# CC2500_Module.net
KiCad netlist of a schematic drawn in EAGLE
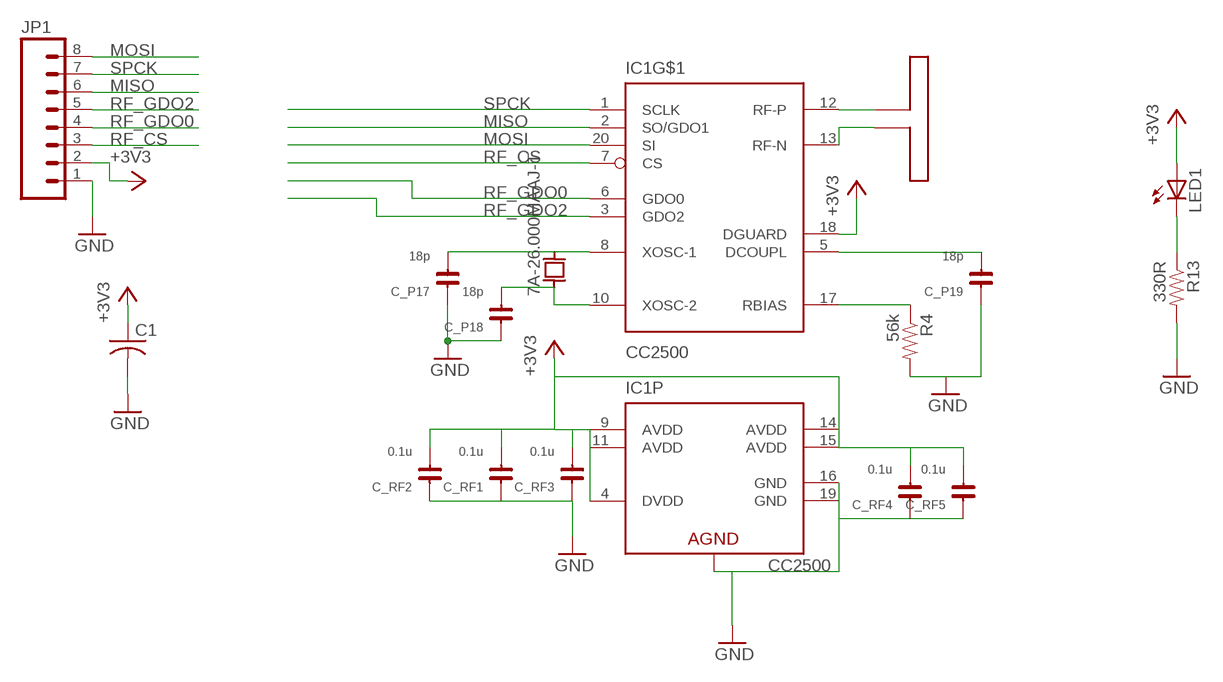
[diagram p0: schematic, sheet 1]

(export (version "E")
  (design (tool "Eeschema 10.0.6"))
  (components
    (comp (ref "C1")
      (value "C-USC1206")
      (footprint "eagle-import:C1206")
      (libsource (lib "eagle-import") (part "C-USC1206"))
    )
    (comp (ref "C_P17")
      (value "18p")
      (footprint "eagle-import:0603-CAP")
      (libsource (lib "eagle-import") (part "CAPACITOR0603-CAP"))
    )
    (comp (ref "C_P18")
      (value "18p")
      (footprint "eagle-import:0603-CAP")
      (libsource (lib "eagle-import") (part "CAPACITOR0603-CAP"))
    )
    (comp (ref "C_P19")
      (value "18p")
      (footprint "eagle-import:0603-CAP")
      (libsource (lib "eagle-import") (part "CAPACITOR0603-CAP"))
    )
    (comp (ref "C_RF1")
      (value "0.1u")
      (footprint "eagle-import:0603-CAP")
      (libsource (lib "eagle-import") (part "CAPACITOR0603-CAP"))
    )
    (comp (ref "C_RF2")
      (value "0.1u")
      (footprint "eagle-import:0603-CAP")
      (libsource (lib "eagle-import") (part "CAPACITOR0603-CAP"))
    )
    (comp (ref "C_RF3")
      (value "0.1u")
      (footprint "eagle-import:0603-CAP")
      (libsource (lib "eagle-import") (part "CAPACITOR0603-CAP"))
    )
    (comp (ref "C_RF4")
      (value "0.1u")
      (footprint "eagle-import:0603-CAP")
      (libsource (lib "eagle-import") (part "CAPACITOR0603-CAP"))
    )
    (comp (ref "C_RF5")
      (value "0.1u")
      (footprint "eagle-import:0603-CAP")
      (libsource (lib "eagle-import") (part "CAPACITOR0603-CAP"))
    )
    (comp (ref "IC1")
      (value "CC2500")
      (footprint "eagle-import:QLP-20")
      (libsource (lib "eagle-import") (part "CC2500"))
    )
    (comp (ref "JP1")
      (value "M081X08")
      (footprint "eagle-import:1X08")
      (libsource (lib "eagle-import") (part "M081X08"))
    )
    (comp (ref "LED1")
      (value "LED1206")
      (footprint "eagle-import:LED-1206")
      (libsource (lib "eagle-import") (part "LED1206"))
    )
    (comp (ref "R4")
      (value "56k")
      (footprint "eagle-import:0402-RES")
      (libsource (lib "eagle-import") (part "RESISTOR0402-RES"))
    )
    (comp (ref "R13")
      (value "330R")
      (footprint "eagle-import:0402-RES")
      (libsource (lib "eagle-import") (part "RESISTOR0402-RES"))
    )
    (comp (ref "U$22")
      (value "ANTENNA_DIPOLE")
      (footprint "eagle-import:CC2500_FOLDED_DIPOLE_ANTENNA")
      (libsource (lib "eagle-import") (part "ANTENNA_DIPOLE"))
    )
    (comp (ref "U$23")
      (value "7A-26.000MAAJ-T")
      (footprint "eagle-import:5X3.2MM_SMD_XTAL")
      (libsource (lib "eagle-import") (part "XTAL_2_PIN5MMX3.2MM"))
    )
  )
  (nets
    (net (code "1") (name "+3V3") (class "Default")
      (node (ref "C1") (pin "1") (pinfunction "1_1") (pintype "passive"))
      (node (ref "C_RF1") (pin "2") (pinfunction "2_2") (pintype "bidirectional"))
      (node (ref "C_RF2") (pin "2") (pinfunction "2_2") (pintype "bidirectional"))
      (node (ref "C_RF3") (pin "2") (pinfunction "2_2") (pintype "bidirectional"))
      (node (ref "C_RF4") (pin "2") (pinfunction "2_2") (pintype "bidirectional"))
      (node (ref "C_RF5") (pin "2") (pinfunction "2_2") (pintype "bidirectional"))
      (node (ref "IC1") (pin "11") (pinfunction "AVDD_11") (pintype "power_in"))
      (node (ref "IC1") (pin "14") (pinfunction "AVDD_14") (pintype "power_in"))
      (node (ref "IC1") (pin "15") (pinfunction "AVDD_15") (pintype "power_in"))
      (node (ref "IC1") (pin "18") (pinfunction "DGUARD_18") (pintype "power_in"))
      (node (ref "IC1") (pin "4") (pinfunction "DVDD_4") (pintype "power_in"))
      (node (ref "IC1") (pin "9") (pinfunction "AVDD_9") (pintype "power_in"))
      (node (ref "JP1") (pin "2") (pinfunction "2_2") (pintype "passive"))
      (node (ref "LED1") (pin "A") (pinfunction "A_A") (pintype "passive"))
    )
    (net (code "2") (name "/MISO") (class "Default")
      (node (ref "IC1") (pin "2") (pinfunction "SO/GDO1_2") (pintype "output"))
      (node (ref "JP1") (pin "6") (pinfunction "6_6") (pintype "passive"))
    )
    (net (code "3") (name "/MOSI") (class "Default")
      (node (ref "IC1") (pin "20") (pinfunction "SI_20") (pintype "input"))
      (node (ref "JP1") (pin "8") (pinfunction "8_8") (pintype "passive"))
    )
    (net (code "4") (name "/RF_CS") (class "Default")
      (node (ref "IC1") (pin "7") (pinfunction "CS_7") (pintype "input"))
      (node (ref "JP1") (pin "3") (pinfunction "3_3") (pintype "passive"))
    )
    (net (code "5") (name "/RF_GDO0") (class "Default")
      (node (ref "IC1") (pin "6") (pinfunction "GDO0_6") (pintype "output"))
      (node (ref "JP1") (pin "4") (pinfunction "4_4") (pintype "passive"))
    )
    (net (code "6") (name "/RF_GDO2") (class "Default")
      (node (ref "IC1") (pin "3") (pinfunction "GDO2_3") (pintype "output"))
      (node (ref "JP1") (pin "5") (pinfunction "5_5") (pintype "passive"))
    )
    (net (code "7") (name "/SPCK") (class "Default")
      (node (ref "IC1") (pin "1") (pinfunction "SCLK_1") (pintype "input"))
      (node (ref "JP1") (pin "7") (pinfunction "7_7") (pintype "passive"))
    )
    (net (code "8") (name "GND") (class "Default")
      (node (ref "C1") (pin "2") (pinfunction "2_2") (pintype "passive"))
      (node (ref "C_P17") (pin "1") (pinfunction "1_1") (pintype "bidirectional"))
      (node (ref "C_P18") (pin "1") (pinfunction "1_1") (pintype "bidirectional"))
      (node (ref "C_P19") (pin "1") (pinfunction "1_1") (pintype "bidirectional"))
      (node (ref "C_RF1") (pin "1") (pinfunction "1_1") (pintype "bidirectional"))
      (node (ref "C_RF2") (pin "1") (pinfunction "1_1") (pintype "bidirectional"))
      (node (ref "C_RF3") (pin "1") (pinfunction "1_1") (pintype "bidirectional"))
      (node (ref "C_RF4") (pin "1") (pinfunction "1_1") (pintype "bidirectional"))
      (node (ref "C_RF5") (pin "1") (pinfunction "1_1") (pintype "bidirectional"))
      (node (ref "IC1") (pin "16") (pinfunction "GND_16") (pintype "power_in"))
      (node (ref "IC1") (pin "19") (pinfunction "GND_19") (pintype "power_in"))
      (node (ref "IC1") (pin "PAD") (pinfunction "AGND_PAD") (pintype "power_in"))
      (node (ref "IC1") (pin "THERMAL1") (pinfunction "AGND_THERMAL1") (pintype "power_in"))
      (node (ref "IC1") (pin "THERMAL2") (pinfunction "AGND_THERMAL2") (pintype "power_in"))
      (node (ref "IC1") (pin "THERMAL3") (pinfunction "AGND_THERMAL3") (pintype "power_in"))
      (node (ref "IC1") (pin "THERMAL4") (pinfunction "AGND_THERMAL4") (pintype "power_in"))
      (node (ref "IC1") (pin "THERMAL5") (pinfunction "AGND_THERMAL5") (pintype "power_in"))
      (node (ref "JP1") (pin "1") (pinfunction "1_1") (pintype "passive"))
      (node (ref "R13") (pin "2") (pinfunction "2_2") (pintype "passive"))
      (node (ref "R4") (pin "2") (pinfunction "2_2") (pintype "passive"))
    )
    (net (code "9") (name "Net-(IC1A-DCOUPL)") (class "Default")
      (node (ref "C_P19") (pin "2") (pinfunction "2_2") (pintype "bidirectional"))
      (node (ref "IC1") (pin "5") (pinfunction "DCOUPL_5") (pintype "power_in"))
    )
    (net (code "10") (name "Net-(IC1A-RBIAS)") (class "Default")
      (node (ref "IC1") (pin "17") (pinfunction "RBIAS_17") (pintype "bidirectional"))
      (node (ref "R4") (pin "1") (pinfunction "1_1") (pintype "passive"))
    )
    (net (code "11") (name "Net-(IC1A-RF-N)") (class "Default")
      (node (ref "IC1") (pin "13") (pinfunction "RF-N_13") (pintype "bidirectional"))
      (node (ref "U$22") (pin "P$2") (pinfunction "P$2_P$2") (pintype "bidirectional"))
    )
    (net (code "12") (name "Net-(IC1A-RF-P)") (class "Default")
      (node (ref "IC1") (pin "12") (pinfunction "RF-P_12") (pintype "bidirectional"))
      (node (ref "U$22") (pin "P$1") (pinfunction "P$1_P$1") (pintype "bidirectional"))
    )
    (net (code "13") (name "Net-(IC1A-XOSC-1)") (class "Default")
      (node (ref "C_P17") (pin "2") (pinfunction "2_2") (pintype "bidirectional"))
      (node (ref "IC1") (pin "8") (pinfunction "XOSC-1_8") (pintype "input"))
      (node (ref "U$23") (pin "X2") (pinfunction "X2_X2") (pintype "bidirectional"))
    )
    (net (code "14") (name "Net-(IC1A-XOSC-2)") (class "Default")
      (node (ref "C_P18") (pin "2") (pinfunction "2_2") (pintype "bidirectional"))
      (node (ref "IC1") (pin "10") (pinfunction "XOSC-2_10") (pintype "output"))
      (node (ref "U$23") (pin "X1") (pinfunction "X1_X1") (pintype "bidirectional"))
    )
    (net (code "15") (name "Net-(LED1-PadC)") (class "Default")
      (node (ref "LED1") (pin "C") (pinfunction "C_C") (pintype "passive"))
      (node (ref "R13") (pin "1") (pinfunction "1_1") (pintype "passive"))
    )
  )
)
